# ButtonBuffering.net
KiCad netlist of a schematic drawn in Altium Designer
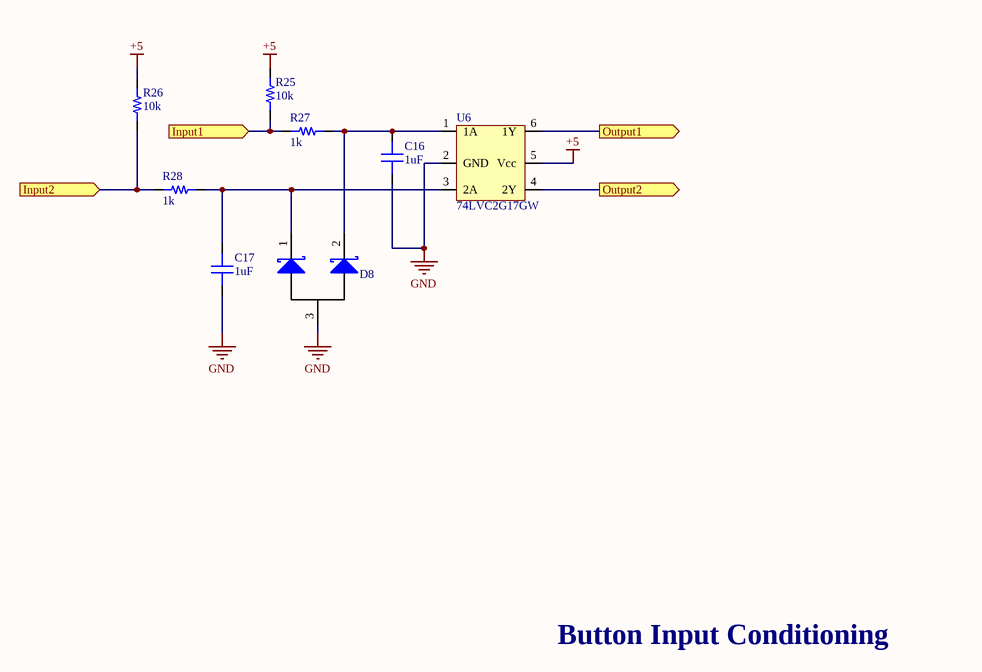
[diagram p0: ButtonBuffering.SchDoc]

(export (version "E")
  (design (tool "Eeschema 10.0.6"))
  (components
    (comp (ref "C16")
      (value "capacitor")
      (footprint "0603")
      (description "Generic 0603 capacitor")
      (fields (field (name "CAPACITANCE") "1uF") (field (name "VOLTAGE") "50"))
      (libsource (lib "altlib") (part "capacitor"))
    )
    (comp (ref "C17")
      (value "capacitor")
      (footprint "0603")
      (description "Generic 0603 capacitor")
      (fields (field (name "CAPACITANCE") "1uF") (field (name "VOLTAGE") "50"))
      (libsource (lib "altlib") (part "capacitor"))
    )
    (comp (ref "D8")
      (value "AZ23C4V7-7-F Dual Zenner Diodes")
      (footprint "SOT23-3")
      (description "DIODE ZENER ARRAY 4.7V SOT23-3")
      (libsource (lib "altlib") (part "AZ23C4V7-7-F Dual Zenner Diodes"))
    )
    (comp (ref "R25")
      (value "10k")
      (footprint "RES 0603/1608")
      (fields (field (name "RESISTANCE") "10k"))
      (libsource (lib "altlib") (part "Resistor"))
    )
    (comp (ref "R26")
      (value "10k")
      (footprint "RES 0603/1608")
      (fields (field (name "RESISTANCE") "10k"))
      (libsource (lib "altlib") (part "Resistor"))
    )
    (comp (ref "R27")
      (value "1k")
      (footprint "RES 0603/1608")
      (fields (field (name "RESISTANCE") "1k"))
      (libsource (lib "altlib") (part "Resistor"))
    )
    (comp (ref "R28")
      (value "1k")
      (footprint "RES 0603/1608")
      (fields (field (name "RESISTANCE") "1k"))
      (libsource (lib "altlib") (part "Resistor"))
    )
    (comp (ref "U6")
      (value "74LVC2G17GW")
      (footprint "TSOP95P280X110-6N")
      (description "Buffer, Non-Inverting 2 Element 1 Bit per Element Push-Pull Output 6-TSSOP")
      (fields (field (name "CREATEDBY") "Nolan") (field (name "UPDATEDBY") "Nolan"))
      (libsource (lib "altlib") (part "74LVC2G17GW"))
    )
  )
  (nets
    (net (code "1") (name "+5") (class "Default")
      (node (ref "R25") (pin "2") (pinfunction "2_2") (pintype "passive"))
      (node (ref "R26") (pin "2") (pinfunction "2_2") (pintype "passive"))
      (node (ref "U6") (pin "5") (pinfunction "Vcc_5") (pintype "passive"))
    )
    (net (code "2") (name "/Input1") (class "Default")
      (node (ref "R25") (pin "1") (pinfunction "1_1") (pintype "passive"))
      (node (ref "R27") (pin "1") (pinfunction "1_1") (pintype "passive"))
    )
    (net (code "3") (name "/Input2") (class "Default")
      (node (ref "R26") (pin "1") (pinfunction "1_1") (pintype "passive"))
      (node (ref "R28") (pin "1") (pinfunction "1_1") (pintype "passive"))
    )
    (net (code "4") (name "/Output1") (class "Default")
      (node (ref "U6") (pin "6") (pinfunction "1Y_6") (pintype "passive"))
    )
    (net (code "5") (name "/Output2") (class "Default")
      (node (ref "U6") (pin "4") (pinfunction "2Y_4") (pintype "passive"))
    )
    (net (code "6") (name "GND") (class "Default")
      (node (ref "C16") (pin "1") (pinfunction "1_1") (pintype "passive"))
      (node (ref "C17") (pin "1") (pinfunction "1_1") (pintype "passive"))
      (node (ref "D8") (pin "3") (pinfunction "3_3") (pintype "passive"))
      (node (ref "U6") (pin "2") (pinfunction "GND_2") (pintype "passive"))
    )
    (net (code "7") (name "Net-(U6-1A)") (class "Default")
      (node (ref "C16") (pin "2") (pinfunction "2_2") (pintype "passive"))
      (node (ref "D8") (pin "2") (pinfunction "2_2") (pintype "passive"))
      (node (ref "R27") (pin "2") (pinfunction "2_2") (pintype "passive"))
      (node (ref "U6") (pin "1") (pinfunction "1A_1") (pintype "passive"))
    )
    (net (code "8") (name "Net-(U6-2A)") (class "Default")
      (node (ref "C17") (pin "2") (pinfunction "2_2") (pintype "passive"))
      (node (ref "D8") (pin "1") (pinfunction "1_1") (pintype "passive"))
      (node (ref "R28") (pin "2") (pinfunction "2_2") (pintype "passive"))
      (node (ref "U6") (pin "3") (pinfunction "2A_3") (pintype "passive"))
    )
  )
)
